# Sensor_Sheet.net
KiCad netlist of a schematic drawn in Altium Designer
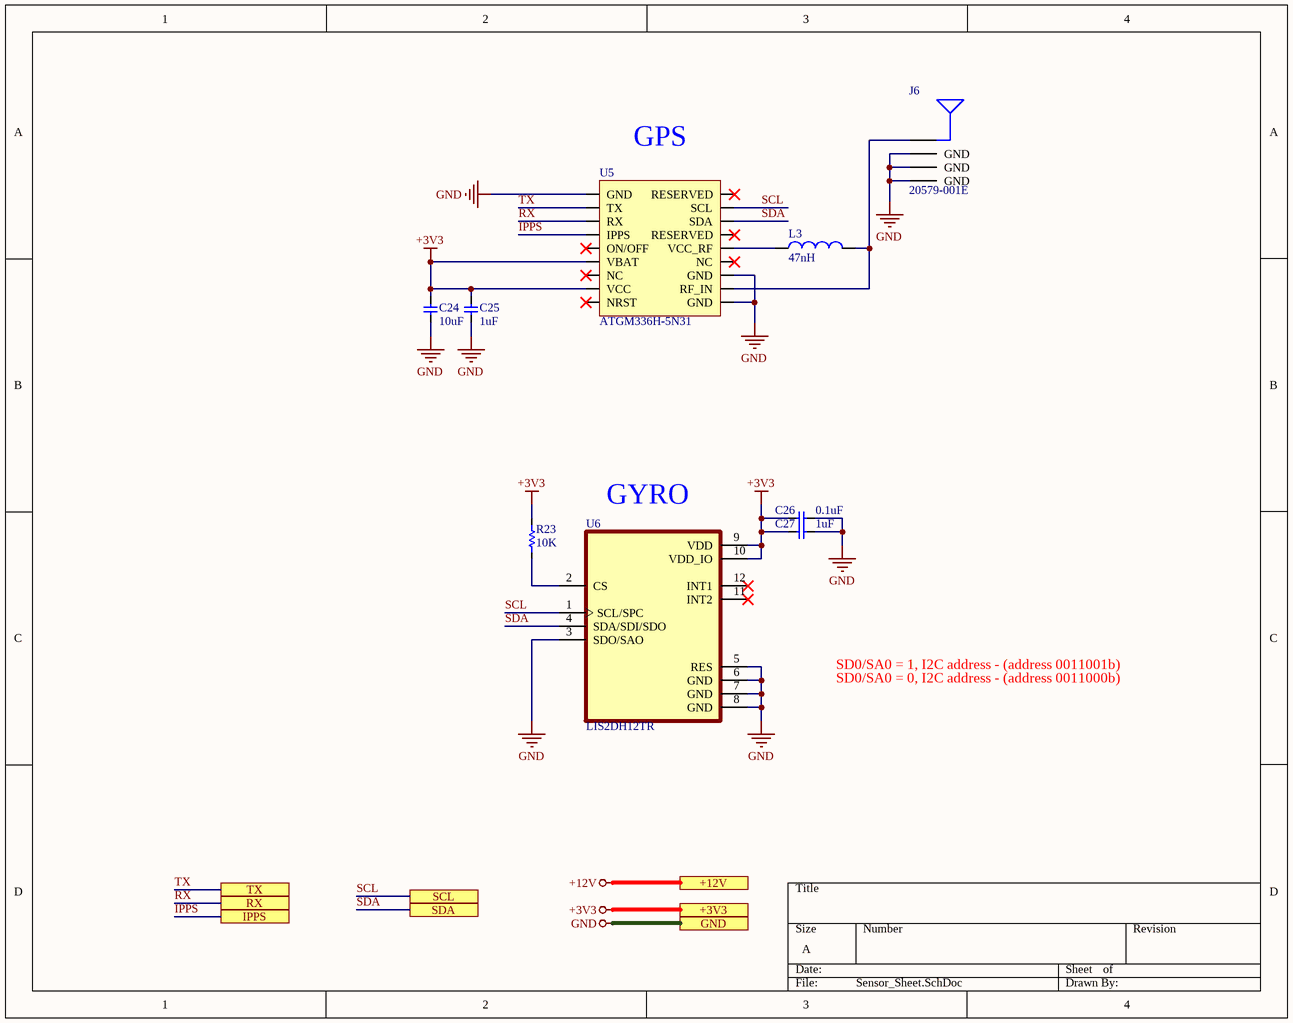
[diagram p0: Sensor_Sheet.SchDoc]

(export (version "E")
  (design (tool "Eeschema 10.0.6"))
  (components
    (comp (ref "C24")
      (value "10uF")
      (footprint "Cap-0603")
      (description "10uF 35V X5R 20% Pad SMD 0603")
      (fields
        (field (name "MANUFACTURER") "Murata")
        (field (name "MANUFACTURER PART NUMBER") "GRM188R6YA106MA73D")
      )
      (libsource (lib "DigitalAzanClock") (part "GRM188R6YA106MA73D"))
    )
    (comp (ref "C25")
      (value "1uF")
      (footprint "Cap-0603")
      (description "CAP CER 1UF 25V X5R 0603")
      (fields
        (field (name "MANUFACTURER") "Yageo")
        (field (name "MANUFACTURER PART NUMBER") "CC0603KRX5R8BB105")
      )
      (libsource (lib "DigitalAzanClock") (part "CC0603KRX5R8BB105"))
    )
    (comp (ref "C26")
      (value "0.1uF")
      (footprint "Cap-0603")
      (description "CAP CER 0.1UF 100V X7R 0603")
      (fields
        (field (name "MANUFACTURER") "Yageo")
        (field (name "MANUFACTURER PART NUMBER") "CC0603KRX7R0BB104")
      )
      (libsource (lib "DigitalAzanClock") (part "CC0603KRX7R0BB104"))
    )
    (comp (ref "C27")
      (value "1uF")
      (footprint "Cap-0603")
      (description "CAP CER 1UF 25V X5R 0603")
      (fields
        (field (name "MANUFACTURER") "Yageo")
        (field (name "MANUFACTURER PART NUMBER") "CC0603KRX5R8BB105")
      )
      (libsource (lib "DigitalAzanClock") (part "CC0603KRX5R8BB105"))
    )
    (comp (ref "J6")
      (value "20579-001E")
      (footprint "IPEX-1")
      (description "The M.2 industry standard,support up to 12 GHz")
      (fields (field (name "MANUFACTURER") "I-PEX") (field (name "LCSC PART NUMBER") "C2987682"))
      (libsource (lib "DigitalAzanClock") (part "IPEX-0001"))
    )
    (comp (ref "L3")
      (value "47nH")
      (footprint "LQG15HS47NJ02D")
      (fields
        (field (name "MANUFACTURER") "Murata Electronics")
        (field (name "MANUFACTURER PART NUMBER") "LQG15HS47NJ02D")
        (field (name "LCSC PART NUMBER") "C97998")
      )
      (libsource (lib "DigitalAzanClock") (part "LQG15HS47NJ02D"))
    )
    (comp (ref "R23")
      (value "10K")
      (footprint "Res-0603")
      (description "RES SMD 10K OHM 0.1% 1/10W 0603")
      (fields
        (field (name "MANUFACTURER") "Yageo")
        (field (name "MANUFACTURER PART NUMBER") "RT0603BRD0710KL")
      )
      (libsource (lib "DigitalAzanClock") (part "RT0603BRD0710KL"))
    )
    (comp (ref "U5")
      (value "ATGM336H-5N31")
      (footprint "ATGM336H")
      (description "SMD,9.7x10.1mm Satellite Positioning Modules ROHS")
      (fields (field (name "MANUFACTURER") "ZHONGKEWEI") (field (name "LCSC PART NUMBER") "C90770"))
      (libsource (lib "DigitalAzanClock") (part "ATGM336H-5N31"))
    )
    (comp (ref "U6")
      (value "LIS2DH12TR")
      (footprint "PQFN50P200X200100-12N")
      (description "Accelerometer X, Y, Z Axis Â±2g, 4g, 8g, 16g 0.5Hz ~ 672Hz 12-LGA (2x2)")
      (fields (field (name "MANUFACTURER") "STMicroelectronics") (field (name "LCSC PART NUMBER") "C110926"))
      (libsource (lib "DigitalAzanClock") (part "LIS2DH12TR"))
    )
  )
  (nets
    (net (code "1") (name "+3V3") (class "Default")
      (node (ref "C24") (pin "2") (pinfunction "2_2") (pintype "passive"))
      (node (ref "C25") (pin "2") (pinfunction "2_2") (pintype "passive"))
      (node (ref "C26") (pin "1") (pinfunction "1_1") (pintype "passive"))
      (node (ref "C27") (pin "1") (pinfunction "1_1") (pintype "passive"))
      (node (ref "R23") (pin "2") (pinfunction "2_2") (pintype "passive"))
      (node (ref "U5") (pin "6") (pinfunction "VBAT_6") (pintype "passive"))
      (node (ref "U5") (pin "8") (pinfunction "VCC_8") (pintype "passive"))
      (node (ref "U6") (pin "10") (pinfunction "VDD_IO_10") (pintype "power_in"))
      (node (ref "U6") (pin "9") (pinfunction "VDD_9") (pintype "power_in"))
    )
    (net (code "3") (name "/IPPS") (class "Default")
      (node (ref "U5") (pin "4") (pinfunction "IPPS_4") (pintype "passive"))
    )
    (net (code "4") (name "/RX") (class "Default")
      (node (ref "U5") (pin "3") (pinfunction "RX_3") (pintype "passive"))
    )
    (net (code "5") (name "/SCL") (class "Default")
      (node (ref "U5") (pin "17") (pinfunction "SCL_17") (pintype "passive"))
      (node (ref "U6") (pin "1") (pinfunction "SCL/SPC_1") (pintype "passive"))
    )
    (net (code "6") (name "/SDA") (class "Default")
      (node (ref "U5") (pin "16") (pinfunction "SDA_16") (pintype "passive"))
      (node (ref "U6") (pin "4") (pinfunction "SDA/SDI/SDO_4") (pintype "passive"))
    )
    (net (code "7") (name "/TX") (class "Default")
      (node (ref "U5") (pin "2") (pinfunction "TX_2") (pintype "passive"))
    )
    (net (code "8") (name "GND") (class "Default")
      (node (ref "C24") (pin "1") (pinfunction "1_1") (pintype "passive"))
      (node (ref "C25") (pin "1") (pinfunction "1_1") (pintype "passive"))
      (node (ref "C26") (pin "2") (pinfunction "2_2") (pintype "passive"))
      (node (ref "C27") (pin "2") (pinfunction "2_2") (pintype "passive"))
      (node (ref "J6") (pin "1") (pinfunction "GND_1") (pintype "passive"))
      (node (ref "J6") (pin "2") (pinfunction "GND_2") (pintype "passive"))
      (node (ref "J6") (pin "3") (pinfunction "GND_3") (pintype "passive"))
      (node (ref "U5") (pin "1") (pinfunction "GND_1") (pintype "passive"))
      (node (ref "U5") (pin "10") (pinfunction "GND_10") (pintype "passive"))
      (node (ref "U5") (pin "12") (pinfunction "GND_12") (pintype "passive"))
      (node (ref "U6") (pin "3") (pinfunction "SDO/SAO_3") (pintype "passive"))
      (node (ref "U6") (pin "5") (pinfunction "RES_5") (pintype "power_in"))
      (node (ref "U6") (pin "6") (pinfunction "GND_6") (pintype "power_in"))
      (node (ref "U6") (pin "7") (pinfunction "GND_7") (pintype "power_in"))
      (node (ref "U6") (pin "8") (pinfunction "GND_8") (pintype "power_in"))
    )
    (net (code "9") (name "Net-(J6-SIGNAL)") (class "Default")
      (node (ref "J6") (pin "4") (pinfunction "SIGNAL_4") (pintype "passive"))
      (node (ref "L3") (pin "2") (pinfunction "2_2") (pintype "passive"))
      (node (ref "U5") (pin "11") (pinfunction "RF_IN_11") (pintype "passive"))
    )
    (net (code "10") (name "Net-(U5-VCC_RF)") (class "Default")
      (node (ref "L3") (pin "1") (pinfunction "1_1") (pintype "passive"))
      (node (ref "U5") (pin "14") (pinfunction "VCC_RF_14") (pintype "passive"))
    )
    (net (code "11") (name "Net-(U6-CS)") (class "Default")
      (node (ref "R23") (pin "1") (pinfunction "1_1") (pintype "passive"))
      (node (ref "U6") (pin "2") (pinfunction "CS_2") (pintype "passive"))
    )
    (net (code "12") (name "unconnected-(U5-NC-Pad7)") (class "Default")
      (node (ref "U5") (pin "7") (pinfunction "NC_7") (pintype "passive+no_connect"))
    )
    (net (code "13") (name "unconnected-(U5-NC-Pad13)") (class "Default")
      (node (ref "U5") (pin "13") (pinfunction "NC_13") (pintype "passive+no_connect"))
    )
    (net (code "14") (name "unconnected-(U5-NRST-Pad9)") (class "Default")
      (node (ref "U5") (pin "9") (pinfunction "NRST_9") (pintype "passive+no_connect"))
    )
    (net (code "15") (name "unconnected-(U5-ON{slash}OFF-Pad5)") (class "Default")
      (node (ref "U5") (pin "5") (pinfunction "ON/OFF_5") (pintype "passive+no_connect"))
    )
    (net (code "16") (name "unconnected-(U5-RESERVED-Pad15)") (class "Default")
      (node (ref "U5") (pin "15") (pinfunction "RESERVED_15") (pintype "passive+no_connect"))
    )
    (net (code "17") (name "unconnected-(U5-RESERVED-Pad18)") (class "Default")
      (node (ref "U5") (pin "18") (pinfunction "RESERVED_18") (pintype "passive+no_connect"))
    )
    (net (code "18") (name "unconnected-(U6-INT1-Pad12)") (class "Default")
      (node (ref "U6") (pin "12") (pinfunction "INT1_12") (pintype "passive+no_connect"))
    )
    (net (code "19") (name "unconnected-(U6-INT2-Pad11)") (class "Default")
      (node (ref "U6") (pin "11") (pinfunction "INT2_11") (pintype "passive+no_connect"))
    )
  )
)
